# Prism_Controls.net
KiCad netlist of a schematic drawn in EAGLE
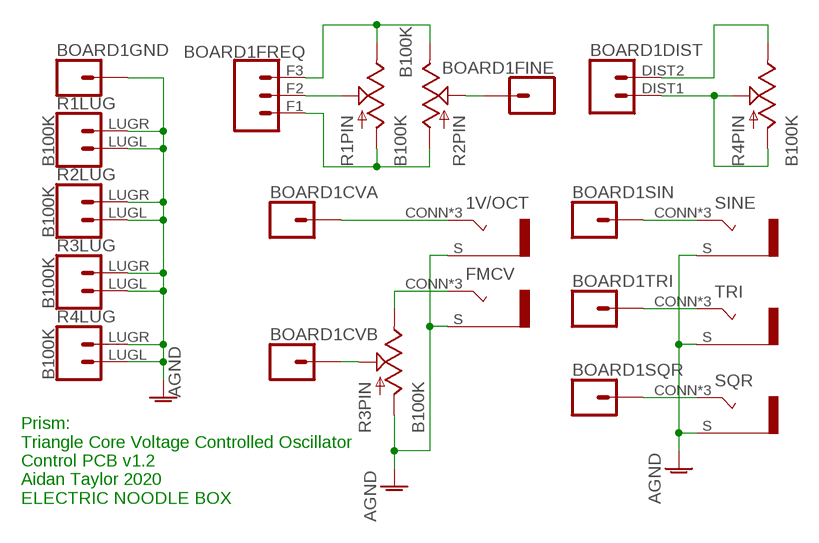
[diagram p0: schematic, sheet 1]

(export (version "E")
  (design (tool "Eeschema 10.0.6"))
  (components
    (comp (ref "1V/OCT")
      (value "COMBI-JACKCINCHNANA")
      (footprint "eagle-import:NEWCOMBOJACK_PANEL")
      (libsource (lib "eagle-import") (part "COMBI-JACKCINCHNANA"))
    )
    (comp (ref "BOARD1")
      (value "PRISM_LINK")
      (footprint "eagle-import:PRISM")
      (libsource (lib "eagle-import") (part "PRISM_LINK"))
    )
    (comp (ref "FMCV")
      (value "COMBI-JACKCINCHNANA")
      (footprint "eagle-import:NEWCOMBOJACK_PANEL")
      (libsource (lib "eagle-import") (part "COMBI-JACKCINCHNANA"))
    )
    (comp (ref "R1")
      (value "B100K")
      (footprint "eagle-import:ALPHA_RV09_9MMPOT")
      (libsource (lib "eagle-import") (part "POTENTIOMETER"))
    )
    (comp (ref "R2")
      (value "B100K")
      (footprint "eagle-import:ALPHA_RV09_9MMPOT")
      (libsource (lib "eagle-import") (part "POTENTIOMETER"))
    )
    (comp (ref "R3")
      (value "B100K")
      (footprint "eagle-import:ALPHA_RV09_9MMPOT")
      (libsource (lib "eagle-import") (part "POTENTIOMETER"))
    )
    (comp (ref "R4")
      (value "B100K")
      (footprint "eagle-import:ALPHA_RV09_9MMPOT")
      (libsource (lib "eagle-import") (part "POTENTIOMETER"))
    )
    (comp (ref "SINE")
      (value "COMBI-JACKCINCHNANA")
      (footprint "eagle-import:NEWCOMBOJACK_PANEL")
      (libsource (lib "eagle-import") (part "COMBI-JACKCINCHNANA"))
    )
    (comp (ref "SQR")
      (value "COMBI-JACKCINCHNANA")
      (footprint "eagle-import:NEWCOMBOJACK_PANEL")
      (libsource (lib "eagle-import") (part "COMBI-JACKCINCHNANA"))
    )
    (comp (ref "TRI")
      (value "COMBI-JACKCINCHNANA")
      (footprint "eagle-import:NEWCOMBOJACK_PANEL")
      (libsource (lib "eagle-import") (part "COMBI-JACKCINCHNANA"))
    )
  )
  (nets
    (net (code "1") (name "AGND") (class "Default")
      (node (ref "1V/OCT") (pin "S") (pinfunction "S_S") (pintype "passive"))
      (node (ref "BOARD1") (pin "GNDA") (pinfunction "1_GNDA") (pintype "passive"))
      (node (ref "BOARD1") (pin "GNDB") (pinfunction "1_GNDB") (pintype "passive"))
      (node (ref "FMCV") (pin "S") (pinfunction "S_S") (pintype "passive"))
      (node (ref "R1") (pin "LUGL") (pinfunction "1_LUGL") (pintype "passive"))
      (node (ref "R1") (pin "LUGR") (pinfunction "2_LUGR") (pintype "passive"))
      (node (ref "R2") (pin "LUGL") (pinfunction "1_LUGL") (pintype "passive"))
      (node (ref "R2") (pin "LUGR") (pinfunction "2_LUGR") (pintype "passive"))
      (node (ref "R3") (pin "C1") (pinfunction "A_C1") (pintype "passive"))
      (node (ref "R3") (pin "LUGL") (pinfunction "1_LUGL") (pintype "passive"))
      (node (ref "R3") (pin "LUGR") (pinfunction "2_LUGR") (pintype "passive"))
      (node (ref "R4") (pin "LUGL") (pinfunction "1_LUGL") (pintype "passive"))
      (node (ref "R4") (pin "LUGR") (pinfunction "2_LUGR") (pintype "passive"))
      (node (ref "SINE") (pin "S") (pinfunction "S_S") (pintype "passive"))
      (node (ref "SQR") (pin "S") (pinfunction "S_S") (pintype "passive"))
      (node (ref "TRI") (pin "S") (pinfunction "S_S") (pintype "passive"))
    )
    (net (code "2") (name "Net-(BOARD1A-1)") (class "Default")
      (node (ref "1V/OCT") (pin "CONN") (pinfunction "T_CONN") (pintype "passive"))
      (node (ref "1V/OCT") (pin "T1") (pinfunction "T_T1") (pintype "passive"))
      (node (ref "1V/OCT") (pin "T2") (pinfunction "T_T2") (pintype "passive"))
      (node (ref "BOARD1") (pin "CVA") (pinfunction "1_CVA") (pintype "passive"))
    )
    (net (code "3") (name "Net-(BOARD1B-1)") (class "Default")
      (node (ref "BOARD1") (pin "CVB") (pinfunction "1_CVB") (pintype "passive"))
      (node (ref "R3") (pin "C2") (pinfunction "W_C2") (pintype "passive"))
    )
    (net (code "4") (name "Net-(BOARD1C-1)") (class "Default")
      (node (ref "BOARD1") (pin "DIST1") (pinfunction "1_DIST1") (pintype "passive"))
      (node (ref "R4") (pin "C1") (pinfunction "A_C1") (pintype "passive"))
      (node (ref "R4") (pin "C2") (pinfunction "W_C2") (pintype "passive"))
    )
    (net (code "5") (name "Net-(BOARD1C-2)") (class "Default")
      (node (ref "BOARD1") (pin "DIST2") (pinfunction "2_DIST2") (pintype "passive"))
      (node (ref "R4") (pin "C3") (pinfunction "B_C3") (pintype "passive"))
    )
    (net (code "6") (name "Net-(BOARD1D-1)") (class "Default")
      (node (ref "BOARD1") (pin "FINE") (pinfunction "1_FINE") (pintype "passive"))
      (node (ref "R2") (pin "C2") (pinfunction "W_C2") (pintype "passive"))
    )
    (net (code "7") (name "Net-(BOARD1E-1)") (class "Default")
      (node (ref "BOARD1") (pin "F1") (pinfunction "1_F1") (pintype "passive"))
      (node (ref "R1") (pin "C1") (pinfunction "A_C1") (pintype "passive"))
      (node (ref "R2") (pin "C1") (pinfunction "A_C1") (pintype "passive"))
    )
    (net (code "8") (name "Net-(BOARD1E-2)") (class "Default")
      (node (ref "BOARD1") (pin "F2") (pinfunction "2_F2") (pintype "passive"))
      (node (ref "R1") (pin "C2") (pinfunction "W_C2") (pintype "passive"))
    )
    (net (code "9") (name "Net-(BOARD1E-3)") (class "Default")
      (node (ref "BOARD1") (pin "F3") (pinfunction "3_F3") (pintype "passive"))
      (node (ref "R1") (pin "C3") (pinfunction "B_C3") (pintype "passive"))
      (node (ref "R2") (pin "C3") (pinfunction "B_C3") (pintype "passive"))
    )
    (net (code "10") (name "Net-(BOARD1G-1)") (class "Default")
      (node (ref "BOARD1") (pin "SIN") (pinfunction "1_SIN") (pintype "passive"))
      (node (ref "SINE") (pin "CONN") (pinfunction "T_CONN") (pintype "passive"))
      (node (ref "SINE") (pin "T1") (pinfunction "T_T1") (pintype "passive"))
      (node (ref "SINE") (pin "T2") (pinfunction "T_T2") (pintype "passive"))
    )
    (net (code "11") (name "Net-(BOARD1H-1)") (class "Default")
      (node (ref "BOARD1") (pin "SQR") (pinfunction "1_SQR") (pintype "passive"))
      (node (ref "SQR") (pin "CONN") (pinfunction "T_CONN") (pintype "passive"))
      (node (ref "SQR") (pin "T1") (pinfunction "T_T1") (pintype "passive"))
      (node (ref "SQR") (pin "T2") (pinfunction "T_T2") (pintype "passive"))
    )
    (net (code "12") (name "Net-(BOARD1I-1)") (class "Default")
      (node (ref "BOARD1") (pin "TRI") (pinfunction "1_TRI") (pintype "passive"))
      (node (ref "TRI") (pin "CONN") (pinfunction "T_CONN") (pintype "passive"))
      (node (ref "TRI") (pin "T1") (pinfunction "T_T1") (pintype "passive"))
      (node (ref "TRI") (pin "T2") (pinfunction "T_T2") (pintype "passive"))
    )
    (net (code "13") (name "Net-(R3B-B)") (class "Default")
      (node (ref "FMCV") (pin "CONN") (pinfunction "T_CONN") (pintype "passive"))
      (node (ref "FMCV") (pin "T1") (pinfunction "T_T1") (pintype "passive"))
      (node (ref "FMCV") (pin "T2") (pinfunction "T_T2") (pintype "passive"))
      (node (ref "R3") (pin "C3") (pinfunction "B_C3") (pintype "passive"))
    )
  )
)
